# Overview.net
KiCad netlist of a schematic drawn in Altium Designer
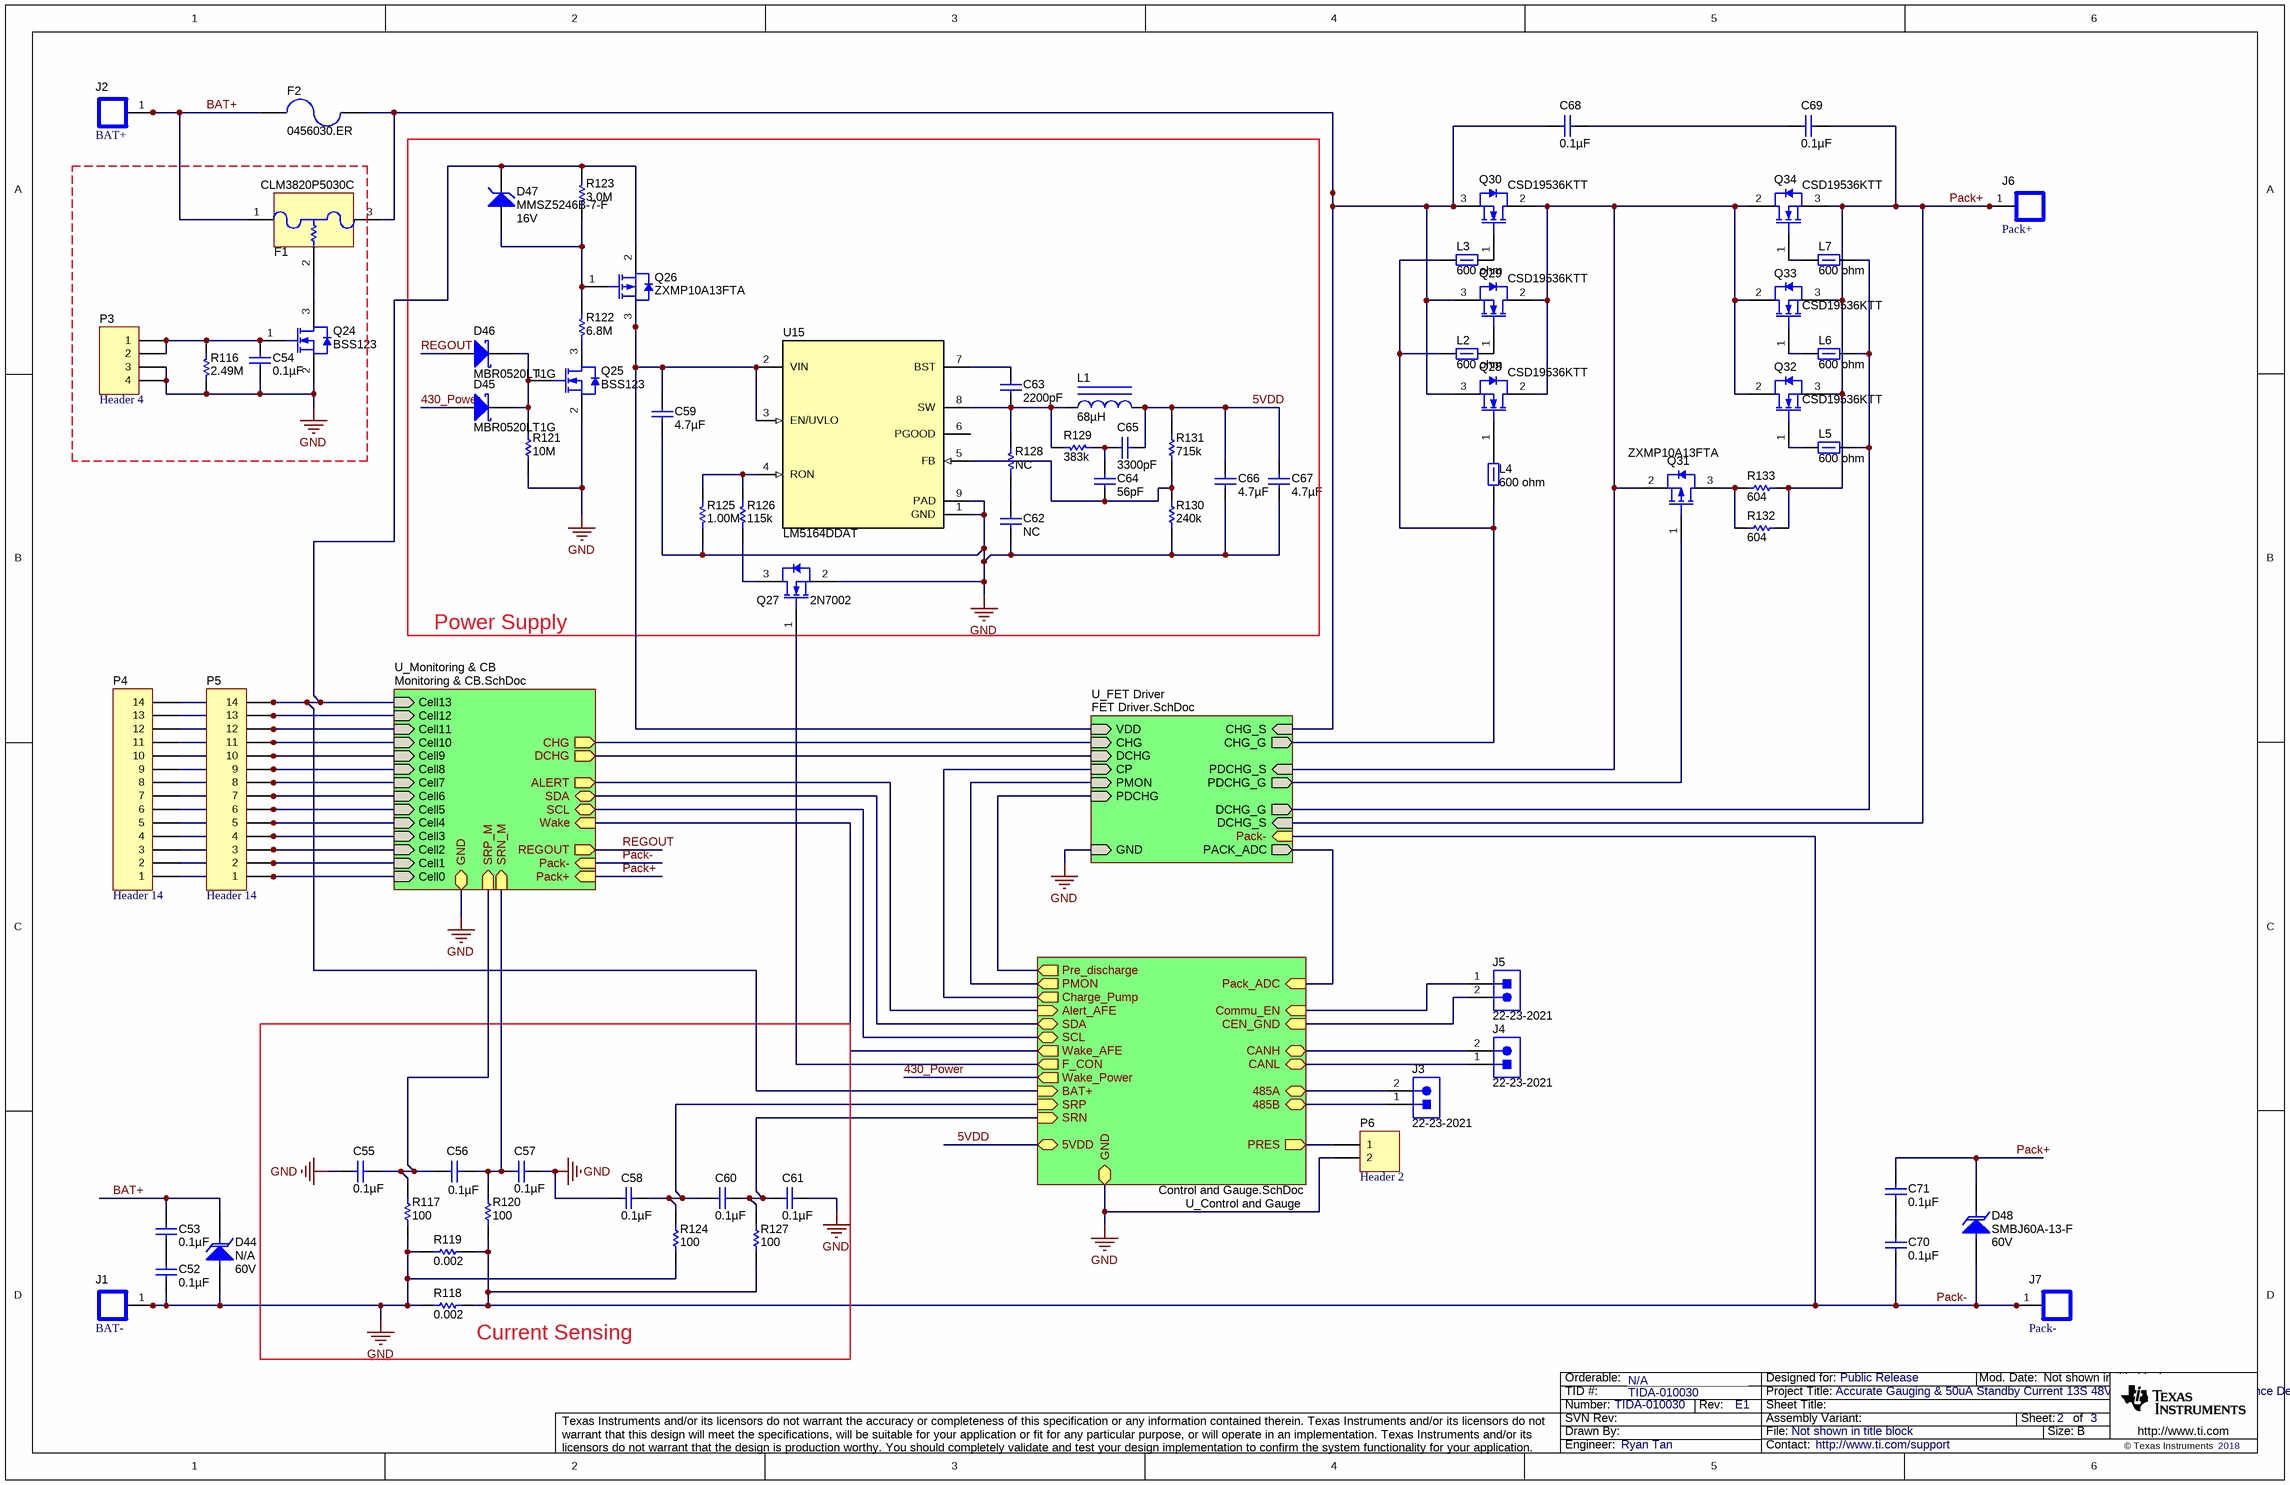
[diagram p0: Overview.SchDoc]

(export (version "E")
  (design (tool "Eeschema 10.0.6"))
  (components
    (comp (ref "C52")
      (value "GRM188R72A104KA35D")
      (footprint "0603")
      (description "CAP, CERM, 0.1 µF, 100 V,+/- 10%, X7R, 0603")
      (fields
        (field (name "VALUEDISPLAYED") "0.1µF")
        (field (name "MANUFACTURER") "MuRata")
        (field (name "PUBLISHER") "Texas Instruments")
      )
      (libsource (lib "Capacitor_Ceramic") (part "GRM188R72A104KA35D"))
    )
    (comp (ref "C53")
      (value "GRM188R72A104KA35D")
      (footprint "0603")
      (description "CAP, CERM, 0.1 µF, 100 V,+/- 10%, X7R, 0603")
      (fields
        (field (name "VALUEDISPLAYED") "0.1µF")
        (field (name "MANUFACTURER") "MuRata")
        (field (name "PUBLISHER") "Texas Instruments")
      )
      (libsource (lib "Capacitor_Ceramic") (part "GRM188R72A104KA35D"))
    )
    (comp (ref "C54")
      (value "GRM188R71H104KA93D")
      (footprint "0603")
      (description "CAP, CERM, 0.1 µF, 50 V,+/- 10%, X7R, 0603")
      (fields
        (field (name "VALUEDISPLAYED") "0.1µF")
        (field (name "MANUFACTURER") "MuRata")
        (field (name "PUBLISHER") "Texas Instruments")
      )
      (libsource (lib "Capacitor_Ceramic") (part "GRM188R71H104KA93D"))
    )
    (comp (ref "C55")
      (value "GRM188R71H104KA93D")
      (footprint "0603")
      (description "CAP, CERM, 0.1 µF, 50 V,+/- 10%, X7R, 0603")
      (fields
        (field (name "VALUEDISPLAYED") "0.1µF")
        (field (name "MANUFACTURER") "MuRata")
        (field (name "PUBLISHER") "Texas Instruments")
      )
      (libsource (lib "Capacitor_Ceramic") (part "GRM188R71H104KA93D"))
    )
    (comp (ref "C56")
      (value "GRM188R71H104KA93D")
      (footprint "0603")
      (description "CAP, CERM, 0.1 µF, 50 V,+/- 10%, X7R, 0603")
      (fields
        (field (name "VALUEDISPLAYED") "0.1µF")
        (field (name "MANUFACTURER") "MuRata")
        (field (name "PUBLISHER") "Texas Instruments")
      )
      (libsource (lib "Capacitor_Ceramic") (part "GRM188R71H104KA93D"))
    )
    (comp (ref "C57")
      (value "GRM188R71H104KA93D")
      (footprint "0603")
      (description "CAP, CERM, 0.1 µF, 50 V,+/- 10%, X7R, 0603")
      (fields
        (field (name "VALUEDISPLAYED") "0.1µF")
        (field (name "MANUFACTURER") "MuRata")
        (field (name "PUBLISHER") "Texas Instruments")
      )
      (libsource (lib "Capacitor_Ceramic") (part "GRM188R71H104KA93D"))
    )
    (comp (ref "C58")
      (value "GRM188R71H104KA93D")
      (footprint "0603")
      (description "CAP, CERM, 0.1 µF, 50 V,+/- 10%, X7R, 0603")
      (fields
        (field (name "VALUEDISPLAYED") "0.1µF")
        (field (name "MANUFACTURER") "MuRata")
        (field (name "PUBLISHER") "Texas Instruments")
      )
      (libsource (lib "Capacitor_Ceramic") (part "GRM188R71H104KA93D"))
    )
    (comp (ref "C59")
      (value "C3225X7S2A475K200AE")
      (footprint "1210")
      (description "CAP, CERM, 4.7 µF, 100 V,+/- 10%, X7S, 1210")
      (fields
        (field (name "VALUEDISPLAYED") "4.7µF")
        (field (name "MANUFACTURER") "TDK")
        (field (name "PUBLISHER") "Texas Instruments")
      )
      (libsource (lib "Capacitor_Ceramic") (part "C3225X7S2A475K200AE"))
    )
    (comp (ref "C60")
      (value "GRM188R71H104KA93D")
      (footprint "0603")
      (description "CAP, CERM, 0.1 µF, 50 V,+/- 10%, X7R, 0603")
      (fields
        (field (name "VALUEDISPLAYED") "0.1µF")
        (field (name "MANUFACTURER") "MuRata")
        (field (name "PUBLISHER") "Texas Instruments")
      )
      (libsource (lib "Capacitor_Ceramic") (part "GRM188R71H104KA93D"))
    )
    (comp (ref "C61")
      (value "GRM188R71H104KA93D")
      (footprint "0603")
      (description "CAP, CERM, 0.1 µF, 50 V,+/- 10%, X7R, 0603")
      (fields
        (field (name "VALUEDISPLAYED") "0.1µF")
        (field (name "MANUFACTURER") "MuRata")
        (field (name "PUBLISHER") "Texas Instruments")
      )
      (libsource (lib "Capacitor_Ceramic") (part "GRM188R71H104KA93D"))
    )
    (comp (ref "C62")
      (value "GRM1885C1H560JA01D")
      (footprint "0603")
      (description "NC")
      (fields
        (field (name "VALUEDISPLAYED") "NC")
        (field (name "MANUFACTURER") "MuRata")
        (field (name "PUBLISHER") "Texas Instruments")
      )
      (libsource (lib "Capacitor_Ceramic") (part "GRM1885C1H560JA01D"))
    )
    (comp (ref "C63")
      (value "GRM1885C1H222JA01D")
      (footprint "0603")
      (description "CAP, CERM, 2200 pF, 50 V,+/- 5%, C0G/NP0, 0603")
      (fields
        (field (name "VALUEDISPLAYED") "2200pF")
        (field (name "MANUFACTURER") "MuRata")
        (field (name "PUBLISHER") "Texas Instruments")
      )
      (libsource (lib "Capacitor_Ceramic") (part "GRM1885C1H222JA01D"))
    )
    (comp (ref "C64")
      (value "GRM1885C1H560JA01D")
      (footprint "0603")
      (description "CAP, CERM, 56 pF, 50 V,+/- 5%, C0G/NP0, 0603")
      (fields
        (field (name "VALUEDISPLAYED") "56pF")
        (field (name "MANUFACTURER") "MuRata")
        (field (name "PUBLISHER") "Texas Instruments")
      )
      (libsource (lib "Capacitor_Ceramic") (part "GRM1885C1H560JA01D"))
    )
    (comp (ref "C65")
      (value "GRM188R71H332KA01D")
      (footprint "0603")
      (description "CAP, CERM, 3300 pF, 50 V,+/- 10%, X7R, 0603")
      (fields
        (field (name "VALUEDISPLAYED") "3300pF")
        (field (name "MANUFACTURER") "MuRata")
        (field (name "PUBLISHER") "Texas Instruments")
      )
      (libsource (lib "Capacitor_Ceramic") (part "GRM188R71H332KA01D"))
    )
    (comp (ref "C66")
      (value "GRM21BR71C475KA73L")
      (footprint "0805_HV")
      (description "CAP, CERM, 4.7 µF, 16 V,+/- 10%, X7R, 0805")
      (fields
        (field (name "VALUEDISPLAYED") "4.7µF")
        (field (name "MANUFACTURER") "MuRata")
        (field (name "PUBLISHER") "Texas Instruments")
      )
      (libsource (lib "Capacitor_Ceramic") (part "GRM21BR71C475KA73L"))
    )
    (comp (ref "C67")
      (value "GRM21BR71C475KA73L")
      (footprint "0805_HV")
      (description "CAP, CERM, 4.7 µF, 16 V,+/- 10%, X7R, 0805")
      (fields
        (field (name "VALUEDISPLAYED") "4.7µF")
        (field (name "MANUFACTURER") "MuRata")
        (field (name "PUBLISHER") "Texas Instruments")
      )
      (libsource (lib "Capacitor_Ceramic") (part "GRM21BR71C475KA73L"))
    )
    (comp (ref "C68")
      (value "GRM188R72A104KA35D")
      (footprint "0603")
      (description "CAP, CERM, 0.1 µF, 100 V,+/- 10%, X7R, 0603")
      (fields
        (field (name "VALUEDISPLAYED") "0.1µF")
        (field (name "MANUFACTURER") "MuRata")
        (field (name "PUBLISHER") "Texas Instruments")
      )
      (libsource (lib "Capacitor_Ceramic") (part "GRM188R72A104KA35D"))
    )
    (comp (ref "C69")
      (value "GRM188R72A104KA35D")
      (footprint "0603")
      (description "CAP, CERM, 0.1 µF, 100 V,+/- 10%, X7R, 0603")
      (fields
        (field (name "VALUEDISPLAYED") "0.1µF")
        (field (name "MANUFACTURER") "MuRata")
        (field (name "PUBLISHER") "Texas Instruments")
      )
      (libsource (lib "Capacitor_Ceramic") (part "GRM188R72A104KA35D"))
    )
    (comp (ref "C70")
      (value "GRM188R72A104KA35D")
      (footprint "0603")
      (description "CAP, CERM, 0.1 µF, 100 V,+/- 10%, X7R, 0603")
      (fields
        (field (name "VALUEDISPLAYED") "0.1µF")
        (field (name "MANUFACTURER") "MuRata")
        (field (name "PUBLISHER") "Texas Instruments")
      )
      (libsource (lib "Capacitor_Ceramic") (part "GRM188R72A104KA35D"))
    )
    (comp (ref "C71")
      (value "GRM188R72A104KA35D")
      (footprint "0603")
      (description "CAP, CERM, 0.1 µF, 100 V,+/- 10%, X7R, 0603")
      (fields
        (field (name "VALUEDISPLAYED") "0.1µF")
        (field (name "MANUFACTURER") "MuRata")
        (field (name "PUBLISHER") "Texas Instruments")
      )
      (libsource (lib "Capacitor_Ceramic") (part "GRM188R72A104KA35D"))
    )
    (comp (ref "D44")
      (value "N/A")
      (footprint "SMB")
      (description "Diode, TVS, Uni, 60 V, 96.8 Vc, SMB")
      (fields
        (field (name "ALTIUM_VALUE") "60V")
        (field (name "PARTNUMBER") "SMBJ60A-13-F")
        (field (name "MANUFACTURER") "Diodes Inc.")
        (field (name "PUBLISHER") "Texas Instruments")
      )
      (libsource (lib "ZenerDiodes") (part "SMBJ60A-13-F"))
    )
    (comp (ref "D45")
      (value "MBR0520LT1G")
      (footprint "SOD-123")
      (description "Diode, Schottky, 20 V, 0.5 A, SOD-123")
      (fields (field (name "MANUFACTURER") "ON Semiconductor") (field (name "PUBLISHER") "Texas Instruments"))
      (libsource (lib "Diode") (part "MBR0520LT1G"))
    )
    (comp (ref "D46")
      (value "MBR0520LT1G")
      (footprint "SOD-123")
      (description "Diode, Schottky, 20 V, 0.5 A, SOD-123")
      (fields (field (name "MANUFACTURER") "ON Semiconductor") (field (name "PUBLISHER") "Texas Instruments"))
      (libsource (lib "Diode") (part "MBR0520LT1G"))
    )
    (comp (ref "D47")
      (value "MMSZ5246B-7-F")
      (footprint "SOD-123")
      (description "Diode, Zener, 16 V, 500 mW, SOD-123")
      (fields
        (field (name "ALTIUM_VALUE") "16V")
        (field (name "MANUFACTURER") "Diodes Inc.")
        (field (name "SYMBOLCREATOR") "a0412235")
        (field (name "PUBLISHER") "Texas Instruments")
      )
      (libsource (lib "ZenerDiodes") (part "MMSZ5246B-7-F"))
    )
    (comp (ref "D48")
      (value "SMBJ60A-13-F")
      (footprint "SMB")
      (description "Diode, TVS, Uni, 60 V, 96.8 Vc, SMB")
      (fields
        (field (name "ALTIUM_VALUE") "60V")
        (field (name "MANUFACTURER") "Diodes Inc.")
        (field (name "PUBLISHER") "Texas Instruments")
      )
      (libsource (lib "ZenerDiodes") (part "SMBJ60A-13-F"))
    )
    (comp (ref "F1")
      (value "CLM3820P5030C")
      (footprint "FUSE_SFK-xx30x")
      (description "Fuse, 30 A, SMD")
      (fields
        (field (name "MANUFACTURER") "POLYTRONICS")
        (field (name "SYMBOLCREATOR") "x0208325")
        (field (name "PUBLISHER") "Texas Instruments")
      )
      (libsource (lib "Fuse") (part "SFK-5030"))
    )
    (comp (ref "F2")
      (value "0456030.ER")
      (footprint "FUSE_0456030")
      (description "Fuse, 30 A, 125 VAC, 72 VDC, SMD")
      (fields (field (name "MANUFACTURER") "Littelfuse") (field (name "PUBLISHER") "Texas Instruments"))
      (libsource (lib "Fuse") (part "0456030.ER"))
    )
    (comp (ref "J1")
      (value "BAT-")
      (footprint "SCREW_TERMINAL_8199")
      (description "TERMINAL SCREW PC 30AMP, TH")
      (fields
        (field (name "PARTNUMBER") "8199")
        (field (name "MANUFACTURER") "Keystone")
        (field (name "SYMBOLCREATOR") "a0799628")
        (field (name "PUBLISHER") "Texas Instruments")
      )
      (libsource (lib "Connectors_Keystone") (part "8199"))
    )
    (comp (ref "J2")
      (value "BAT+")
      (footprint "SCREW_TERMINAL_8199")
      (description "TERMINAL SCREW PC 30AMP, TH")
      (fields
        (field (name "PARTNUMBER") "8199")
        (field (name "MANUFACTURER") "Keystone")
        (field (name "SYMBOLCREATOR") "a0799628")
        (field (name "PUBLISHER") "Texas Instruments")
      )
      (libsource (lib "Connectors_Keystone") (part "8199"))
    )
    (comp (ref "J3")
      (value "22-23-2021")
      (footprint "Molex_22-23-2021")
      (description "Header, 2.54mm, 2x1, Vertical, TH")
      (fields
        (field (name "MANUFACTURER") "Molex")
        (field (name "SYMBOLCREATOR") "a0412235")
        (field (name "PUBLISHER") "Texas Instruments")
      )
      (libsource (lib "Connectors_Molex") (part "22-23-2021"))
    )
    (comp (ref "J4")
      (value "22-23-2021")
      (footprint "Molex_22-23-2021")
      (description "Header, 2.54mm, 2x1, Vertical, TH")
      (fields
        (field (name "MANUFACTURER") "Molex")
        (field (name "SYMBOLCREATOR") "a0412235")
        (field (name "PUBLISHER") "Texas Instruments")
      )
      (libsource (lib "Connectors_Molex") (part "22-23-2021"))
    )
    (comp (ref "J5")
      (value "22-23-2021")
      (footprint "Molex_22-23-2021")
      (description "Header, 2.54mm, 2x1, Vertical, TH")
      (fields
        (field (name "MANUFACTURER") "Molex")
        (field (name "SYMBOLCREATOR") "a0412235")
        (field (name "PUBLISHER") "Texas Instruments")
      )
      (libsource (lib "") (part "22-23-2021_1"))
    )
    (comp (ref "J6")
      (value "Pack+")
      (footprint "SCREW_TERMINAL_8199")
      (description "TERMINAL SCREW PC 30AMP, TH")
      (fields
        (field (name "PARTNUMBER") "8199")
        (field (name "MANUFACTURER") "Keystone")
        (field (name "SYMBOLCREATOR") "a0799628")
        (field (name "PUBLISHER") "Texas Instruments")
      )
      (libsource (lib "Connectors_Keystone") (part "8199"))
    )
    (comp (ref "J7")
      (value "Pack-")
      (footprint "SCREW_TERMINAL_8199")
      (description "TERMINAL SCREW PC 30AMP, TH")
      (fields
        (field (name "PARTNUMBER") "8199")
        (field (name "MANUFACTURER") "Keystone")
        (field (name "SYMBOLCREATOR") "a0799628")
        (field (name "PUBLISHER") "Texas Instruments")
      )
      (libsource (lib "Connectors_Keystone") (part "8199"))
    )
    (comp (ref "L1")
      (value "7447713680")
      (footprint "WE-PD_1030")
      (description "Inductor, Shielded Drum Core, Ferrite, 68 µH, 1.1 A, 0.275 ohm, SMD")
      (fields
        (field (name "VALUEDISPLAYED") "68µH")
        (field (name "MANUFACTURER") "Wurth Elektronik")
        (field (name "PUBLISHER") "Texas Instruments")
      )
      (libsource (lib "Inductor_Wurth") (part "7447713680"))
    )
    (comp (ref "L2")
      (value "74279265")
      (footprint "0603")
      (description "Ferrite Bead, 600 ohm @ 100 MHz, 0.2 A, 0603")
      (fields
        (field (name "VALUEDISPLAYED") "600 ohm")
        (field (name "MANUFACTURER") "Wurth Elektronik")
        (field (name "PUBLISHER") "Texas Instruments")
      )
      (libsource (lib "FerriteBead") (part "74279265"))
    )
    (comp (ref "L3")
      (value "74279265")
      (footprint "0603")
      (description "Ferrite Bead, 600 ohm @ 100 MHz, 0.2 A, 0603")
      (fields
        (field (name "VALUEDISPLAYED") "600 ohm")
        (field (name "MANUFACTURER") "Wurth Elektronik")
        (field (name "PUBLISHER") "Texas Instruments")
      )
      (libsource (lib "FerriteBead") (part "74279265"))
    )
    (comp (ref "L4")
      (value "74279265")
      (footprint "0603")
      (description "Ferrite Bead, 600 ohm @ 100 MHz, 0.2 A, 0603")
      (fields
        (field (name "VALUEDISPLAYED") "600 ohm")
        (field (name "MANUFACTURER") "Wurth Elektronik")
        (field (name "PUBLISHER") "Texas Instruments")
      )
      (libsource (lib "") (part "74279265_1"))
    )
    (comp (ref "L5")
      (value "74279265")
      (footprint "0603")
      (description "Ferrite Bead, 600 ohm @ 100 MHz, 0.2 A, 0603")
      (fields
        (field (name "VALUEDISPLAYED") "600 ohm")
        (field (name "MANUFACTURER") "Wurth Elektronik")
        (field (name "PUBLISHER") "Texas Instruments")
      )
      (libsource (lib "FerriteBead") (part "74279265"))
    )
    (comp (ref "L6")
      (value "74279265")
      (footprint "0603")
      (description "Ferrite Bead, 600 ohm @ 100 MHz, 0.2 A, 0603")
      (fields
        (field (name "VALUEDISPLAYED") "600 ohm")
        (field (name "MANUFACTURER") "Wurth Elektronik")
        (field (name "PUBLISHER") "Texas Instruments")
      )
      (libsource (lib "FerriteBead") (part "74279265"))
    )
    (comp (ref "L7")
      (value "74279265")
      (footprint "0603")
      (description "Ferrite Bead, 600 ohm @ 100 MHz, 0.2 A, 0603")
      (fields
        (field (name "VALUEDISPLAYED") "600 ohm")
        (field (name "MANUFACTURER") "Wurth Elektronik")
        (field (name "PUBLISHER") "Texas Instruments")
      )
      (libsource (lib "FerriteBead") (part "74279265"))
    )
    (comp (ref "P3")
      (value "Header 4")
      (footprint "HDR1X4")
      (description "Header, 4-Pin")
      (fields (field (name "PUBLISHER") "Altium Limited"))
      (libsource (lib "Miscellaneous Connectors") (part "Header 4"))
    )
    (comp (ref "P4")
      (value "Header 14")
      (footprint "HDR1X14")
      (description "Header, 14-Pin")
      (fields (field (name "PUBLISHER") "Altium Limited"))
      (libsource (lib "Miscellaneous Connectors") (part "Header 14"))
    )
    (comp (ref "P5")
      (value "Header 14")
      (footprint "HDR1X14")
      (description "Header, 14-Pin")
      (fields (field (name "PUBLISHER") "Altium Limited"))
      (libsource (lib "Miscellaneous Connectors") (part "Header 14"))
    )
    (comp (ref "P6")
      (value "Header 2")
      (footprint "HDR1X2")
      (description "Header, 2-Pin")
      (fields (field (name "PUBLISHER") "Altium Limited"))
      (libsource (lib "Miscellaneous Connectors") (part "Header 2"))
    )
    (comp (ref "Q24")
      (value "BSS123")
      (footprint "SOT-23")
      (description "MOSFET, N-CH, 100 V, 0.17 A, SOT-23")
      (fields
        (field (name "MANUFACTURER") "Fairchild Semiconductor")
        (field (name "PUBLISHER") "Texas Instruments")
      )
      (libsource (lib "FETs") (part "BSS123"))
    )
    (comp (ref "Q25")
      (value "BSS123")
      (footprint "SOT-23")
      (description "MOSFET, N-CH, 100 V, 0.17 A, SOT-23")
      (fields
        (field (name "MANUFACTURER") "Fairchild Semiconductor")
        (field (name "PUBLISHER") "Texas Instruments")
      )
      (libsource (lib "FETs") (part "BSS123"))
    )
    (comp (ref "Q26")
      (value "ZXMP10A13FTA")
      (footprint "SOT-23")
      (description "MOSFET, P-CH, -100 V, -0.6 A, SOT-23")
      (fields (field (name "MANUFACTURER") "Diodes Inc.") (field (name "PUBLISHER") "Texas Instruments"))
      (libsource (lib "FETs") (part "ZXMP10A13FTA"))
    )
    (comp (ref "Q27")
      (value "2N7002")
      (footprint "SOT-23")
      (description "MOSFET, N-CH, 60 V, 115 A, SOT-23")
      (fields
        (field (name "MANUFACTURER") "Fairchild Semiconductor")
        (field (name "PUBLISHER") "Texas Instruments")
      )
      (libsource (lib "FETs") (part "2N7002"))
    )
    (comp (ref "Q28")
      (value "CSD19536KTT")
      (footprint "KTT0002A_N")
      (description "MOSFET, N-CH, 100 V, 200 A, KTT0002A (TO-263-2)")
      (fields
        (field (name "MANUFACTURER") "Texas Instruments")
        (field (name "PUBLISHER") "Texas Instruments")
      )
      (libsource (lib "FETs") (part "CSD19536KTT"))
    )
    (comp (ref "Q29")
      (value "CSD19536KTT")
      (footprint "KTT0002A_N")
      (description "MOSFET, N-CH, 100 V, 200 A, KTT0002A (TO-263-2)")
      (fields
        (field (name "MANUFACTURER") "Texas Instruments")
        (field (name "PUBLISHER") "Texas Instruments")
      )
      (libsource (lib "FETs") (part "CSD19536KTT"))
    )
    (comp (ref "Q30")
      (value "CSD19536KTT")
      (footprint "KTT0002A_N")
      (description "MOSFET, N-CH, 100 V, 200 A, KTT0002A (TO-263-2)")
      (fields
        (field (name "MANUFACTURER") "Texas Instruments")
        (field (name "PUBLISHER") "Texas Instruments")
      )
      (libsource (lib "FETs") (part "CSD19536KTT"))
    )
    (comp (ref "Q31")
      (value "ZXMP10A13FTA")
      (footprint "SOT-23")
      (description "MOSFET, P-CH, -100 V, -0.6 A, SOT-23")
      (fields (field (name "MANUFACTURER") "Diodes Inc.") (field (name "PUBLISHER") "Texas Instruments"))
      (libsource (lib "FETs") (part "ZXMP10A13FTA"))
    )
    (comp (ref "Q32")
      (value "CSD19536KTT")
      (footprint "KTT0002A_N")
      (description "MOSFET, N-CH, 100 V, 200 A, KTT0002A (TO-263-2)")
      (fields
        (field (name "MANUFACTURER") "Texas Instruments")
        (field (name "PUBLISHER") "Texas Instruments")
      )
      (libsource (lib "FETs") (part "CSD19536KTT"))
    )
    (comp (ref "Q33")
      (value "CSD19536KTT")
      (footprint "KTT0002A_N")
      (description "MOSFET, N-CH, 100 V, 200 A, KTT0002A (TO-263-2)")
      (fields
        (field (name "MANUFACTURER") "Texas Instruments")
        (field (name "PUBLISHER") "Texas Instruments")
      )
      (libsource (lib "FETs") (part "CSD19536KTT"))
    )
    (comp (ref "Q34")
      (value "CSD19536KTT")
      (footprint "KTT0002A_N")
      (description "MOSFET, N-CH, 100 V, 200 A, KTT0002A (TO-263-2)")
      (fields
        (field (name "MANUFACTURER") "Texas Instruments")
        (field (name "PUBLISHER") "Texas Instruments")
      )
      (libsource (lib "FETs") (part "CSD19536KTT"))
    )
    (comp (ref "R116")
      (value "CRCW06032M49FKEA")
      (footprint "0603")
      (description "RES, 2.49 M, 1%, 0.1 W, 0603")
      (fields
        (field (name "VALUEDISPLAYED") "2.49M")
        (field (name "MANUFACTURER") "Vishay-Dale")
        (field (name "PUBLISHER") "Texas Instruments")
      )
      (libsource (lib "Resistor_0603") (part "CRCW06032M49FKEA"))
    )
    (comp (ref "R117")
      (value "CRCW0603100RFKEA")
      (footprint "0603")
      (description "RES, 100, 1%, 0.1 W, 0603")
      (fields
        (field (name "VALUEDISPLAYED") "100")
        (field (name "MANUFACTURER") "Vishay-Dale")
        (field (name "PUBLISHER") "Texas Instruments")
      )
      (libsource (lib "Resistor_0603") (part "CRCW0603100RFKEA"))
    )
    (comp (ref "R118")
      (value "CSNL2512FT2L00")
      (footprint "2512")
      (description "RES, 0.002, 1%, 2 W, 2512")
      (fields
        (field (name "VALUEDISPLAYED") "0.002")
        (field (name "MANUFACTURER") "Stackpole Electronics Inc")
        (field (name "PUBLISHER") "Texas Instruments")
      )
      (libsource (lib "Resistor_2512") (part "CSNL2512FT2L00"))
    )
    (comp (ref "R119")
      (value "CSNL2512FT2L00")
      (footprint "2512")
      (description "RES, 0.002, 1%, 2 W, 2512")
      (fields
        (field (name "VALUEDISPLAYED") "0.002")
        (field (name "MANUFACTURER") "Stackpole Electronics Inc")
        (field (name "PUBLISHER") "Texas Instruments")
      )
      (libsource (lib "Resistor_2512") (part "CSNL2512FT2L00"))
    )
    (comp (ref "R120")
      (value "CRCW0603100RFKEA")
      (footprint "0603")
      (description "RES, 100, 1%, 0.1 W, 0603")
      (fields
        (field (name "VALUEDISPLAYED") "100")
        (field (name "MANUFACTURER") "Vishay-Dale")
        (field (name "PUBLISHER") "Texas Instruments")
      )
      (libsource (lib "Resistor_0603") (part "CRCW0603100RFKEA"))
    )
    (comp (ref "R121")
      (value "CRCW060310M0JNEA")
      (footprint "0603")
      (description "RES, 10 M, 5%, 0.1 W, 0603")
      (fields
        (field (name "VALUEDISPLAYED") "10M")
        (field (name "MANUFACTURER") "Vishay-Dale")
        (field (name "PUBLISHER") "Texas Instruments")
      )
      (libsource (lib "Resistor_0603") (part "CRCW060310M0JNEA"))
    )
    (comp (ref "R122")
      (value "CRCW06036M80JNEA")
      (footprint "0603")
      (description "RES, 6.8 M, 5%, 0.1 W, 0603")
      (fields
        (field (name "VALUEDISPLAYED") "6.8M")
        (field (name "MANUFACTURER") "Vishay-Dale")
        (field (name "PUBLISHER") "Texas Instruments")
      )
      (libsource (lib "Resistor_0603") (part "CRCW06036M80JNEA"))
    )
    (comp (ref "R123")
      (value "CRCW06033M00JNEA")
      (footprint "0603")
      (description "RES, 3.0 M, 5%, 0.1 W, 0603")
      (fields
        (field (name "VALUEDISPLAYED") "3.0M")
        (field (name "MANUFACTURER") "Vishay-Dale")
        (field (name "PUBLISHER") "Texas Instruments")
      )
      (libsource (lib "Resistor_0603") (part "CRCW06033M00JNEA"))
    )
    (comp (ref "R124")
      (value "CRCW0603100RFKEA")
      (footprint "0603")
      (description "RES, 100, 1%, 0.1 W, 0603")
      (fields
        (field (name "VALUEDISPLAYED") "100")
        (field (name "MANUFACTURER") "Vishay-Dale")
        (field (name "PUBLISHER") "Texas Instruments")
      )
      (libsource (lib "Resistor_0603") (part "CRCW0603100RFKEA"))
    )
    (comp (ref "R125")
      (value "CRCW06031M00FKEA")
      (footprint "0603")
      (description "RES, 1.00 M, 1%, 0.1 W, 0603")
      (fields
        (field (name "VALUEDISPLAYED") "1.00M")
        (field (name "MANUFACTURER") "Vishay-Dale")
        (field (name "PUBLISHER") "Texas Instruments")
      )
      (libsource (lib "Resistor_0603") (part "CRCW06031M00FKEA"))
    )
    (comp (ref "R126")
      (value "CRCW0603115KFKEA")
      (footprint "0603")
      (description "RES, 115 k, 1%, 0.1 W, 0603")
      (fields
        (field (name "VALUEDISPLAYED") "115k")
        (field (name "MANUFACTURER") "Vishay-Dale")
        (field (name "PUBLISHER") "Texas Instruments")
      )
      (libsource (lib "Resistor_0603") (part "CRCW0603115KFKEA"))
    )
    (comp (ref "R127")
      (value "CRCW0603100RFKEA")
      (footprint "0603")
      (description "RES, 100, 1%, 0.1 W, 0603")
      (fields
        (field (name "VALUEDISPLAYED") "100")
        (field (name "MANUFACTURER") "Vishay-Dale")
        (field (name "PUBLISHER") "Texas Instruments")
      )
      (libsource (lib "Resistor_0603") (part "CRCW0603100RFKEA"))
    )
    (comp (ref "R128")
      (value "RC0603FR-07383KL")
      (footprint "0603")
      (description "NC")
      (fields
        (field (name "VALUEDISPLAYED") "NC")
        (field (name "MANUFACTURER") "Yageo America")
        (field (name "PUBLISHER") "Texas Instruments")
      )
      (libsource (lib "Resistor_0603") (part "RC0603FR-07383KL"))
    )
    (comp (ref "R129")
      (value "RC0603FR-07383KL")
      (footprint "0603")
      (description "RES, 383 k, 1%, 0.1 W, 0603")
      (fields
        (field (name "VALUEDISPLAYED") "383k")
        (field (name "MANUFACTURER") "Yageo America")
        (field (name "PUBLISHER") "Texas Instruments")
      )
      (libsource (lib "Resistor_0603") (part "RC0603FR-07383KL"))
    )
    (comp (ref "R130")
      (value "CRCW0603240KJNEA")
      (footprint "0603")
      (description "RES, 240 k, 5%, 0.1 W, 0603")
      (fields
        (field (name "VALUEDISPLAYED") "240k")
        (field (name "MANUFACTURER") "Vishay-Dale")
        (field (name "PUBLISHER") "Texas Instruments")
      )
      (libsource (lib "Resistor_0603") (part "CRCW0603240KJNEA"))
    )
    (comp (ref "R131")
      (value "CRCW0603715KFKEA")
      (footprint "0603")
      (description "RES, 715 k, 1%, 0.1 W, 0603")
      (fields
        (field (name "VALUEDISPLAYED") "715k")
        (field (name "MANUFACTURER") "Vishay-Dale")
        (field (name "PUBLISHER") "Texas Instruments")
      )
      (libsource (lib "Resistor_0603") (part "CRCW0603715KFKEA"))
    )
    (comp (ref "R132")
      (value "CRCW2512604RFKEG")
      (footprint "2512")
      (description "RES, 604, 1%, 1 W, AEC-Q200 Grade 0, 2512")
      (fields
        (field (name "VALUEDISPLAYED") "604")
        (field (name "MANUFACTURER") "Vishay-Dale")
        (field (name "PUBLISHER") "Texas Instruments")
      )
      (libsource (lib "Resistor_2512") (part "CRCW2512604RFKEG"))
    )
    (comp (ref "R133")
      (value "CRCW2512604RFKEG")
      (footprint "2512")
      (description "RES, 604, 1%, 1 W, AEC-Q200 Grade 0, 2512")
      (fields
        (field (name "VALUEDISPLAYED") "604")
        (field (name "MANUFACTURER") "Vishay-Dale")
        (field (name "PUBLISHER") "Texas Instruments")
      )
      (libsource (lib "Resistor_2512") (part "CRCW2512604RFKEG"))
    )
    (comp (ref "U15")
      (value "LM5164DDAT")
      (footprint "DDA0008E_N")
      (description "100-V Low IQ Synchronous Buck Regulator, DDA0008E (SOIC-8)")
      (fields (field (name "MANUFACTURER") "Texas Instruments") (field (name "PARTNUMBER") "LM5164DDAT"))
      (libsource (lib "Altium Vault - TI") (part "LM5164"))
    )
  )
  (nets
    (net (code "1") (name "/5VDD") (class "Default")
      (node (ref "C65") (pin "2") (pinfunction "2_2") (pintype "passive"))
      (node (ref "C66") (pin "1") (pinfunction "1_1") (pintype "passive"))
      (node (ref "C67") (pin "1") (pinfunction "1_1") (pintype "passive"))
      (node (ref "L1") (pin "2") (pinfunction "2_2") (pintype "passive"))
      (node (ref "R131") (pin "2") (pinfunction "2_2") (pintype "passive"))
    )
    (net (code "2") (name "/430_Power") (class "Default")
      (node (ref "D45") (pin "2") (pinfunction "A_2") (pintype "passive"))
    )
    (net (code "3") (name "/485A") (class "Default")
      (node (ref "J3") (pin "2") (pinfunction "2_2") (pintype "passive"))
    )
    (net (code "4") (name "/485B") (class "Default")
      (node (ref "J3") (pin "1") (pinfunction "1_1") (pintype "passive"))
    )
    (net (code "6") (name "/BAT+") (class "Default")
      (node (ref "C53") (pin "1") (pinfunction "1_1") (pintype "passive"))
      (node (ref "D44") (pin "1") (pinfunction "K_1") (pintype "passive"))
      (node (ref "F1") (pin "1") (pinfunction "Fuse_1") (pintype "passive"))
      (node (ref "F2") (pin "2") (pinfunction "2_2") (pintype "passive"))
      (node (ref "J2") (pin "1") (pintype "passive"))
      (node (ref "J2") (pin "2") (pintype "passive"))
      (node (ref "J2") (pin "3") (pintype "passive"))
      (node (ref "J2") (pin "4") (pintype "passive"))
      (node (ref "J2") (pin "5") (pintype "passive"))
      (node (ref "J2") (pin "6") (pintype "passive"))
    )
    (net (code "7") (name "/BAT+_1") (class "Default")
      (node (ref "D47") (pin "1") (pinfunction "K_1") (pintype "passive"))
      (node (ref "P4") (pin "14") (pinfunction "14_14") (pintype "passive"))
      (node (ref "P5") (pin "14") (pinfunction "14_14") (pintype "passive"))
      (node (ref "Q26") (pin "2") (pinfunction "S_2") (pintype "passive"))
      (node (ref "R123") (pin "2") (pinfunction "2_2") (pintype "passive"))
    )
    (net (code "8") (name "/CANH") (class "Default")
      (node (ref "J4") (pin "2") (pinfunction "2_2") (pintype "passive"))
    )
    (net (code "9") (name "/CANL") (class "Default")
      (node (ref "J4") (pin "1") (pinfunction "1_1") (pintype "passive"))
    )
    (net (code "10") (name "/CEN_GND") (class "Default")
      (node (ref "J5") (pin "2") (pinfunction "2_2") (pintype "passive"))
    )
    (net (code "12") (name "/CHG_G") (class "Default")
      (node (ref "L2") (pin "1") (pinfunction "1_1") (pintype "passive"))
      (node (ref "L3") (pin "1") (pinfunction "1_1") (pintype "passive"))
      (node (ref "L4") (pin "1") (pinfunction "1_1") (pintype "passive"))
    )
    (net (code "13") (name "/CHG_S") (class "Default")
      (node (ref "C68") (pin "2") (pinfunction "2_2") (pintype "passive"))
      (node (ref "F1") (pin "3") (pinfunction "Fuse_3") (pintype "passive"))
      (node (ref "F2") (pin "1") (pinfunction "1_1") (pintype "passive"))
      (node (ref "Q28") (pin "3") (pinfunction "S_3") (pintype "passive"))
      (node (ref "Q29") (pin "3") (pinfunction "S_3") (pintype "passive"))
      (node (ref "Q30") (pin "3") (pinfunction "S_3") (pintype "passive"))
    )
    (net (code "14") (name "/Cell0") (class "Default")
      (node (ref "P4") (pin "1") (pinfunction "1_1") (pintype "passive"))
      (node (ref "P5") (pin "1") (pinfunction "1_1") (pintype "passive"))
    )
    (net (code "15") (name "/Cell1") (class "Default")
      (node (ref "P4") (pin "2") (pinfunction "2_2") (pintype "passive"))
      (node (ref "P5") (pin "2") (pinfunction "2_2") (pintype "passive"))
    )
    (net (code "16") (name "/Cell2") (class "Default")
      (node (ref "P4") (pin "3") (pinfunction "3_3") (pintype "passive"))
      (node (ref "P5") (pin "3") (pinfunction "3_3") (pintype "passive"))
    )
    (net (code "17") (name "/Cell3") (class "Default")
      (node (ref "P4") (pin "4") (pinfunction "4_4") (pintype "passive"))
      (node (ref "P5") (pin "4") (pinfunction "4_4") (pintype "passive"))
    )
    (net (code "18") (name "/Cell4") (class "Default")
      (node (ref "P4") (pin "5") (pinfunction "5_5") (pintype "passive"))
      (node (ref "P5") (pin "5") (pinfunction "5_5") (pintype "passive"))
    )
    (net (code "19") (name "/Cell5") (class "Default")
      (node (ref "P4") (pin "6") (pinfunction "6_6") (pintype "passive"))
      (node (ref "P5") (pin "6") (pinfunction "6_6") (pintype "passive"))
    )
    (net (code "20") (name "/Cell6") (class "Default")
      (node (ref "P4") (pin "7") (pinfunction "7_7") (pintype "passive"))
      (node (ref "P5") (pin "7") (pinfunction "7_7") (pintype "passive"))
    )
    (net (code "21") (name "/Cell7") (class "Default")
      (node (ref "P4") (pin "8") (pinfunction "8_8") (pintype "passive"))
      (node (ref "P5") (pin "8") (pinfunction "8_8") (pintype "passive"))
    )
    (net (code "22") (name "/Cell8") (class "Default")
      (node (ref "P4") (pin "9") (pinfunction "9_9") (pintype "passive"))
      (node (ref "P5") (pin "9") (pinfunction "9_9") (pintype "passive"))
    )
    (net (code "23") (name "/Cell9") (class "Default")
      (node (ref "P4") (pin "10") (pinfunction "10_10") (pintype "passive"))
      (node (ref "P5") (pin "10") (pinfunction "10_10") (pintype "passive"))
    )
    (net (code "24") (name "/Cell10") (class "Default")
      (node (ref "P4") (pin "11") (pinfunction "11_11") (pintype "passive"))
      (node (ref "P5") (pin "11") (pinfunction "11_11") (pintype "passive"))
    )
    (net (code "25") (name "/Cell11") (class "Default")
      (node (ref "P4") (pin "12") (pinfunction "12_12") (pintype "passive"))
      (node (ref "P5") (pin "12") (pinfunction "12_12") (pintype "passive"))
    )
    (net (code "26") (name "/Cell12") (class "Default")
      (node (ref "P4") (pin "13") (pinfunction "13_13") (pintype "passive"))
      (node (ref "P5") (pin "13") (pinfunction "13_13") (pintype "passive"))
    )
    (net (code "28") (name "/Commu_EN") (class "Default")
      (node (ref "J5") (pin "1") (pinfunction "1_1") (pintype "passive"))
    )
    (net (code "30") (name "/DCHG_G") (class "Default")
      (node (ref "L5") (pin "2") (pinfunction "2_2") (pintype "passive"))
      (node (ref "L6") (pin "2") (pinfunction "2_2") (pintype "passive"))
      (node (ref "L7") (pin "2") (pinfunction "2_2") (pintype "passive"))
    )
    (net (code "31") (name "/F_CON") (class "Default")
      (node (ref "Q27") (pin "1") (pinfunction "G_1") (pintype "passive"))
    )
    (net (code "33") (name "/PDCHG_G") (class "Default")
      (node (ref "Q31") (pin "1") (pinfunction "G_1") (pintype "passive"))
    )
    (net (code "34") (name "/PDCHG_S") (class "Default")
      (node (ref "Q28") (pin "2") (pinfunction "D_2") (pintype "passive"))
      (node (ref "Q29") (pin "2") (pinfunction "D_2") (pintype "passive"))
      (node (ref "Q30") (pin "2") (pinfunction "D_2") (pintype "passive"))
      (node (ref "Q31") (pin "2") (pinfunction "S_2") (pintype "passive"))
      (node (ref "Q32") (pin "2") (pinfunction "D_2") (pintype "passive"))
      (node (ref "Q33") (pin "2") (pinfunction "D_2") (pintype "passive"))
      (node (ref "Q34") (pin "2") (pinfunction "D_2") (pintype "passive"))
    )
    (net (code "36") (name "/PRES") (class "Default")
      (node (ref "P6") (pin "1") (pinfunction "1_1") (pintype "passive"))
    )
    (net (code "37") (name "/Pack+") (class "Default")
      (node (ref "C69") (pin "1") (pinfunction "1_1") (pintype "passive"))
      (node (ref "C71") (pin "1") (pinfunction "1_1") (pintype "passive"))
      (node (ref "D48") (pin "1") (pinfunction "K_1") (pintype "passive"))
      (node (ref "J6") (pin "1") (pintype "passive"))
      (node (ref "J6") (pin "2") (pintype "passive"))
      (node (ref "J6") (pin "3") (pintype "passive"))
      (node (ref "J6") (pin "4") (pintype "passive"))
      (node (ref "J6") (pin "5") (pintype "passive"))
      (node (ref "J6") (pin "6") (pintype "passive"))
      (node (ref "Q32") (pin "3") (pinfunction "S_3") (pintype "passive"))
      (node (ref "Q33") (pin "3") (pinfunction "S_3") (pintype "passive"))
      (node (ref "Q34") (pin "3") (pinfunction "S_3") (pintype "passive"))
      (node (ref "R132") (pin "1") (pinfunction "1_1") (pintype "passive"))
      (node (ref "R133") (pin "1") (pinfunction "1_1") (pintype "passive"))
    )
    (net (code "38") (name "/Pack-") (class "Default")
      (node (ref "C70") (pin "2") (pinfunction "2_2") (pintype "passive"))
      (node (ref "D48") (pin "2") (pinfunction "A_2") (pintype "passive"))
      (node (ref "J7") (pin "1") (pintype "passive"))
      (node (ref "J7") (pin "2") (pintype "passive"))
      (node (ref "J7") (pin "3") (pintype "passive"))
      (node (ref "J7") (pin "4") (pintype "passive"))
      (node (ref "J7") (pin "5") (pintype "passive"))
      (node (ref "J7") (pin "6") (pintype "passive"))
      (node (ref "R118") (pin "2") (pinfunction "2_2") (pintype "passive"))
      (node (ref "R119") (pin "2") (pinfunction "2_2") (pintype "passive"))
      (node (ref "R120") (pin "1") (pinfunction "1_1") (pintype "passive"))
      (node (ref "R127") (pin "1") (pinfunction "1_1") (pintype "passive"))
    )
    (net (code "40") (name "/REGOUT") (class "Default")
      (node (ref "D46") (pin "2") (pinfunction "A_2") (pintype "passive"))
    )
    (net (code "43") (name "/SRN") (class "Default")
      (node (ref "C60") (pin "1") (pinfunction "1_1") (pintype "passive"))
      (node (ref "C61") (pin "2") (pinfunction "2_2") (pintype "passive"))
      (node (ref "R127") (pin "2") (pinfunction "2_2") (pintype "passive"))
    )
    (net (code "44") (name "/SRN_M") (class "Default")
      (node (ref "C56") (pin "1") (pinfunction "1_1") (pintype "passive"))
      (node (ref "C57") (pin "2") (pinfunction "2_2") (pintype "passive"))
      (node (ref "R120") (pin "2") (pinfunction "2_2") (pintype "passive"))
    )
    (net (code "45") (name "/SRP") (class "Default")
      (node (ref "C58") (pin "1") (pinfunction "1_1") (pintype "passive"))
      (node (ref "C60") (pin "2") (pinfunction "2_2") (pintype "passive"))
      (node (ref "R124") (pin "2") (pinfunction "2_2") (pintype "passive"))
    )
    (net (code "46") (name "/SRP_M") (class "Default")
      (node (ref "C55") (pin "1") (pinfunction "1_1") (pintype "passive"))
      (node (ref "C56") (pin "2") (pinfunction "2_2") (pintype "passive"))
      (node (ref "R117") (pin "2") (pinfunction "2_2") (pintype "passive"))
    )
    (net (code "47") (name "/VDD") (class "Default")
      (node (ref "C59") (pin "1") (pinfunction "1_1") (pintype "passive"))
      (node (ref "Q26") (pin "3") (pinfunction "D_3") (pintype "passive"))
      (node (ref "U15") (pin "2") (pinfunction "VIN_2") (pintype "power_in"))
      (node (ref "U15") (pin "3") (pinfunction "EN/UVLO_3") (pintype "input"))
    )
    (net (code "49") (name "GND") (class "Default")
      (node (ref "C52") (pin "2") (pinfunction "2_2") (pintype "passive"))
      (node (ref "C54") (pin "2") (pinfunction "2_2") (pintype "passive"))
      (node (ref "C55") (pin "2") (pinfunction "2_2") (pintype "passive"))
      (node (ref "C57") (pin "1") (pinfunction "1_1") (pintype "passive"))
      (node (ref "C58") (pin "2") (pinfunction "2_2") (pintype "passive"))
      (node (ref "C59") (pin "2") (pinfunction "2_2") (pintype "passive"))
      (node (ref "C61") (pin "1") (pinfunction "1_1") (pintype "passive"))
      (node (ref "C62") (pin "2") (pinfunction "2_2") (pintype "passive"))
      (node (ref "C66") (pin "2") (pinfunction "2_2") (pintype "passive"))
      (node (ref "C67") (pin "2") (pinfunction "2_2") (pintype "passive"))
      (node (ref "D44") (pin "2") (pinfunction "A_2") (pintype "passive"))
      (node (ref "J1") (pin "1") (pintype "passive"))
      (node (ref "J1") (pin "2") (pintype "passive"))
      (node (ref "J1") (pin "3") (pintype "passive"))
      (node (ref "J1") (pin "4") (pintype "passive"))
      (node (ref "J1") (pin "5") (pintype "passive"))
      (node (ref "J1") (pin "6") (pintype "passive"))
      (node (ref "P3") (pin "3") (pinfunction "3_3") (pintype "passive"))
      (node (ref "P3") (pin "4") (pinfunction "4_4") (pintype "passive"))
      (node (ref "P6") (pin "2") (pinfunction "2_2") (pintype "passive"))
      (node (ref "Q24") (pin "2") (pinfunction "S_2") (pintype "passive"))
      (node (ref "Q25") (pin "2") (pinfunction "S_2") (pintype "passive"))
      (node (ref "Q27") (pin "2") (pinfunction "S_2") (pintype "passive"))
      (node (ref "R116") (pin "1") (pinfunction "1_1") (pintype "passive"))
      (node (ref "R117") (pin "1") (pinfunction "1_1") (pintype "passive"))
      (node (ref "R118") (pin "1") (pinfunction "1_1") (pintype "passive"))
      (node (ref "R119") (pin "1") (pinfunction "1_1") (pintype "passive"))
      (node (ref "R121") (pin "1") (pinfunction "1_1") (pintype "passive"))
      (node (ref "R124") (pin "1") (pinfunction "1_1") (pintype "passive"))
      (node (ref "R125") (pin "2") (pinfunction "2_2") (pintype "passive"))
      (node (ref "R130") (pin "1") (pinfunction "1_1") (pintype "passive"))
      (node (ref "U15") (pin "1") (pinfunction "GND_1") (pintype "power_in"))
      (node (ref "U15") (pin "9") (pinfunction "PAD_9") (pintype "passive"))
    )
    (net (code "50") (name "Net-(C52-Pad1)") (class "Default")
      (node (ref "C52") (pin "1") (pinfunction "1_1") (pintype "passive"))
      (node (ref "C53") (pin "2") (pinfunction "2_2") (pintype "passive"))
    )
    (net (code "51") (name "Net-(C62-Pad1)") (class "Default")
      (node (ref "C62") (pin "1") (pinfunction "1_1") (pintype "passive"))
      (node (ref "R128") (pin "1") (pinfunction "1_1") (pintype "passive"))
    )
    (net (code "52") (name "Net-(C64-Pad1)") (class "Default")
      (node (ref "C64") (pin "1") (pinfunction "1_1") (pintype "passive"))
      (node (ref "C65") (pin "1") (pinfunction "1_1") (pintype "passive"))
      (node (ref "R129") (pin "2") (pinfunction "2_2") (pintype "passive"))
    )
    (net (code "53") (name "Net-(C68-Pad1)") (class "Default")
      (node (ref "C68") (pin "1") (pinfunction "1_1") (pintype "passive"))
      (node (ref "C69") (pin "2") (pinfunction "2_2") (pintype "passive"))
    )
    (net (code "54") (name "Net-(C70-Pad1)") (class "Default")
      (node (ref "C70") (pin "1") (pinfunction "1_1") (pintype "passive"))
      (node (ref "C71") (pin "2") (pinfunction "2_2") (pintype "passive"))
    )
    (net (code "55") (name "Net-(D45-K)") (class "Default")
      (node (ref "D45") (pin "1") (pinfunction "K_1") (pintype "passive"))
      (node (ref "D46") (pin "1") (pinfunction "K_1") (pintype "passive"))
      (node (ref "Q25") (pin "1") (pinfunction "G_1") (pintype "passive"))
      (node (ref "R121") (pin "2") (pinfunction "2_2") (pintype "passive"))
    )
    (net (code "56") (name "Net-(D47-A)") (class "Default")
      (node (ref "D47") (pin "2") (pinfunction "A_2") (pintype "passive"))
      (node (ref "Q26") (pin "1") (pinfunction "G_1") (pintype "passive"))
      (node (ref "R122") (pin "2") (pinfunction "2_2") (pintype "passive"))
      (node (ref "R123") (pin "1") (pinfunction "1_1") (pintype "passive"))
    )
    (net (code "57") (name "Net-(F1-Heater)") (class "Default")
      (node (ref "F1") (pin "2") (pinfunction "Heater_2") (pintype "passive"))
      (node (ref "Q24") (pin "3") (pinfunction "D_3") (pintype "passive"))
    )
    (net (code "58") (name "Net-(Q24-G)") (class "Default")
      (node (ref "C54") (pin "1") (pinfunction "1_1") (pintype "passive"))
      (node (ref "P3") (pin "1") (pinfunction "1_1") (pintype "passive"))
      (node (ref "P3") (pin "2") (pinfunction "2_2") (pintype "passive"))
      (node (ref "Q24") (pin "1") (pinfunction "G_1") (pintype "passive"))
      (node (ref "R116") (pin "2") (pinfunction "2_2") (pintype "passive"))
    )
    (net (code "59") (name "Net-(Q25-D)") (class "Default")
      (node (ref "Q25") (pin "3") (pinfunction "D_3") (pintype "passive"))
      (node (ref "R122") (pin "1") (pinfunction "1_1") (pintype "passive"))
    )
    (net (code "60") (name "Net-(Q27-D)") (class "Default")
      (node (ref "Q27") (pin "3") (pinfunction "D_3") (pintype "passive"))
      (node (ref "R126") (pin "2") (pinfunction "2_2") (pintype "passive"))
    )
    (net (code "61") (name "Net-(Q28-G)") (class "Default")
      (node (ref "L4") (pin "2") (pinfunction "2_2") (pintype "passive"))
      (node (ref "Q28") (pin "1") (pinfunction "G_1") (pintype "passive"))
    )
    (net (code "62") (name "Net-(Q29-G)") (class "Default")
      (node (ref "L2") (pin "2") (pinfunction "2_2") (pintype "passive"))
      (node (ref "Q29") (pin "1") (pinfunction "G_1") (pintype "passive"))
    )
    (net (code "63") (name "Net-(Q30-G)") (class "Default")
      (node (ref "L3") (pin "2") (pinfunction "2_2") (pintype "passive"))
      (node (ref "Q30") (pin "1") (pinfunction "G_1") (pintype "passive"))
    )
    (net (code "64") (name "Net-(Q31-D)") (class "Default")
      (node (ref "Q31") (pin "3") (pinfunction "D_3") (pintype "passive"))
      (node (ref "R132") (pin "2") (pinfunction "2_2") (pintype "passive"))
      (node (ref "R133") (pin "2") (pinfunction "2_2") (pintype "passive"))
    )
    (net (code "65") (name "Net-(Q32-G)") (class "Default")
      (node (ref "L5") (pin "1") (pinfunction "1_1") (pintype "passive"))
      (node (ref "Q32") (pin "1") (pinfunction "G_1") (pintype "passive"))
    )
    (net (code "66") (name "Net-(Q33-G)") (class "Default")
      (node (ref "L6") (pin "1") (pinfunction "1_1") (pintype "passive"))
      (node (ref "Q33") (pin "1") (pinfunction "G_1") (pintype "passive"))
    )
    (net (code "67") (name "Net-(Q34-G)") (class "Default")
      (node (ref "L7") (pin "1") (pinfunction "1_1") (pintype "passive"))
      (node (ref "Q34") (pin "1") (pinfunction "G_1") (pintype "passive"))
    )
    (net (code "68") (name "Net-(U15-BST)") (class "Default")
      (node (ref "C63") (pin "1") (pinfunction "1_1") (pintype "passive"))
      (node (ref "U15") (pin "7") (pinfunction "BST_7") (pintype "power_in"))
    )
    (net (code "69") (name "Net-(U15-FB)") (class "Default")
      (node (ref "C64") (pin "2") (pinfunction "2_2") (pintype "passive"))
      (node (ref "R130") (pin "2") (pinfunction "2_2") (pintype "passive"))
      (node (ref "R131") (pin "1") (pinfunction "1_1") (pintype "passive"))
      (node (ref "U15") (pin "5") (pinfunction "FB_5") (pintype "input"))
    )
    (net (code "70") (name "Net-(U15-RON)") (class "Default")
      (node (ref "R125") (pin "1") (pinfunction "1_1") (pintype "passive"))
      (node (ref "R126") (pin "1") (pinfunction "1_1") (pintype "passive"))
      (node (ref "U15") (pin "4") (pinfunction "RON_4") (pintype "input"))
    )
    (net (code "71") (name "Net-(U15-SW)") (class "Default")
      (node (ref "C63") (pin "2") (pinfunction "2_2") (pintype "passive"))
      (node (ref "L1") (pin "1") (pinfunction "1_1") (pintype "passive"))
      (node (ref "R128") (pin "2") (pinfunction "2_2") (pintype "passive"))
      (node (ref "R129") (pin "1") (pinfunction "1_1") (pintype "passive"))
      (node (ref "U15") (pin "8") (pinfunction "SW_8") (pintype "power_in"))
    )
    (net (code "72") (name "unconnected-(U15-PGOOD-Pad6)") (class "Default")
      (node (ref "U15") (pin "6") (pinfunction "PGOOD_6") (pintype "open_collector"))
    )
  )
)
